# SCH.net
KiCad netlist of a schematic drawn in EasyEDA Pro
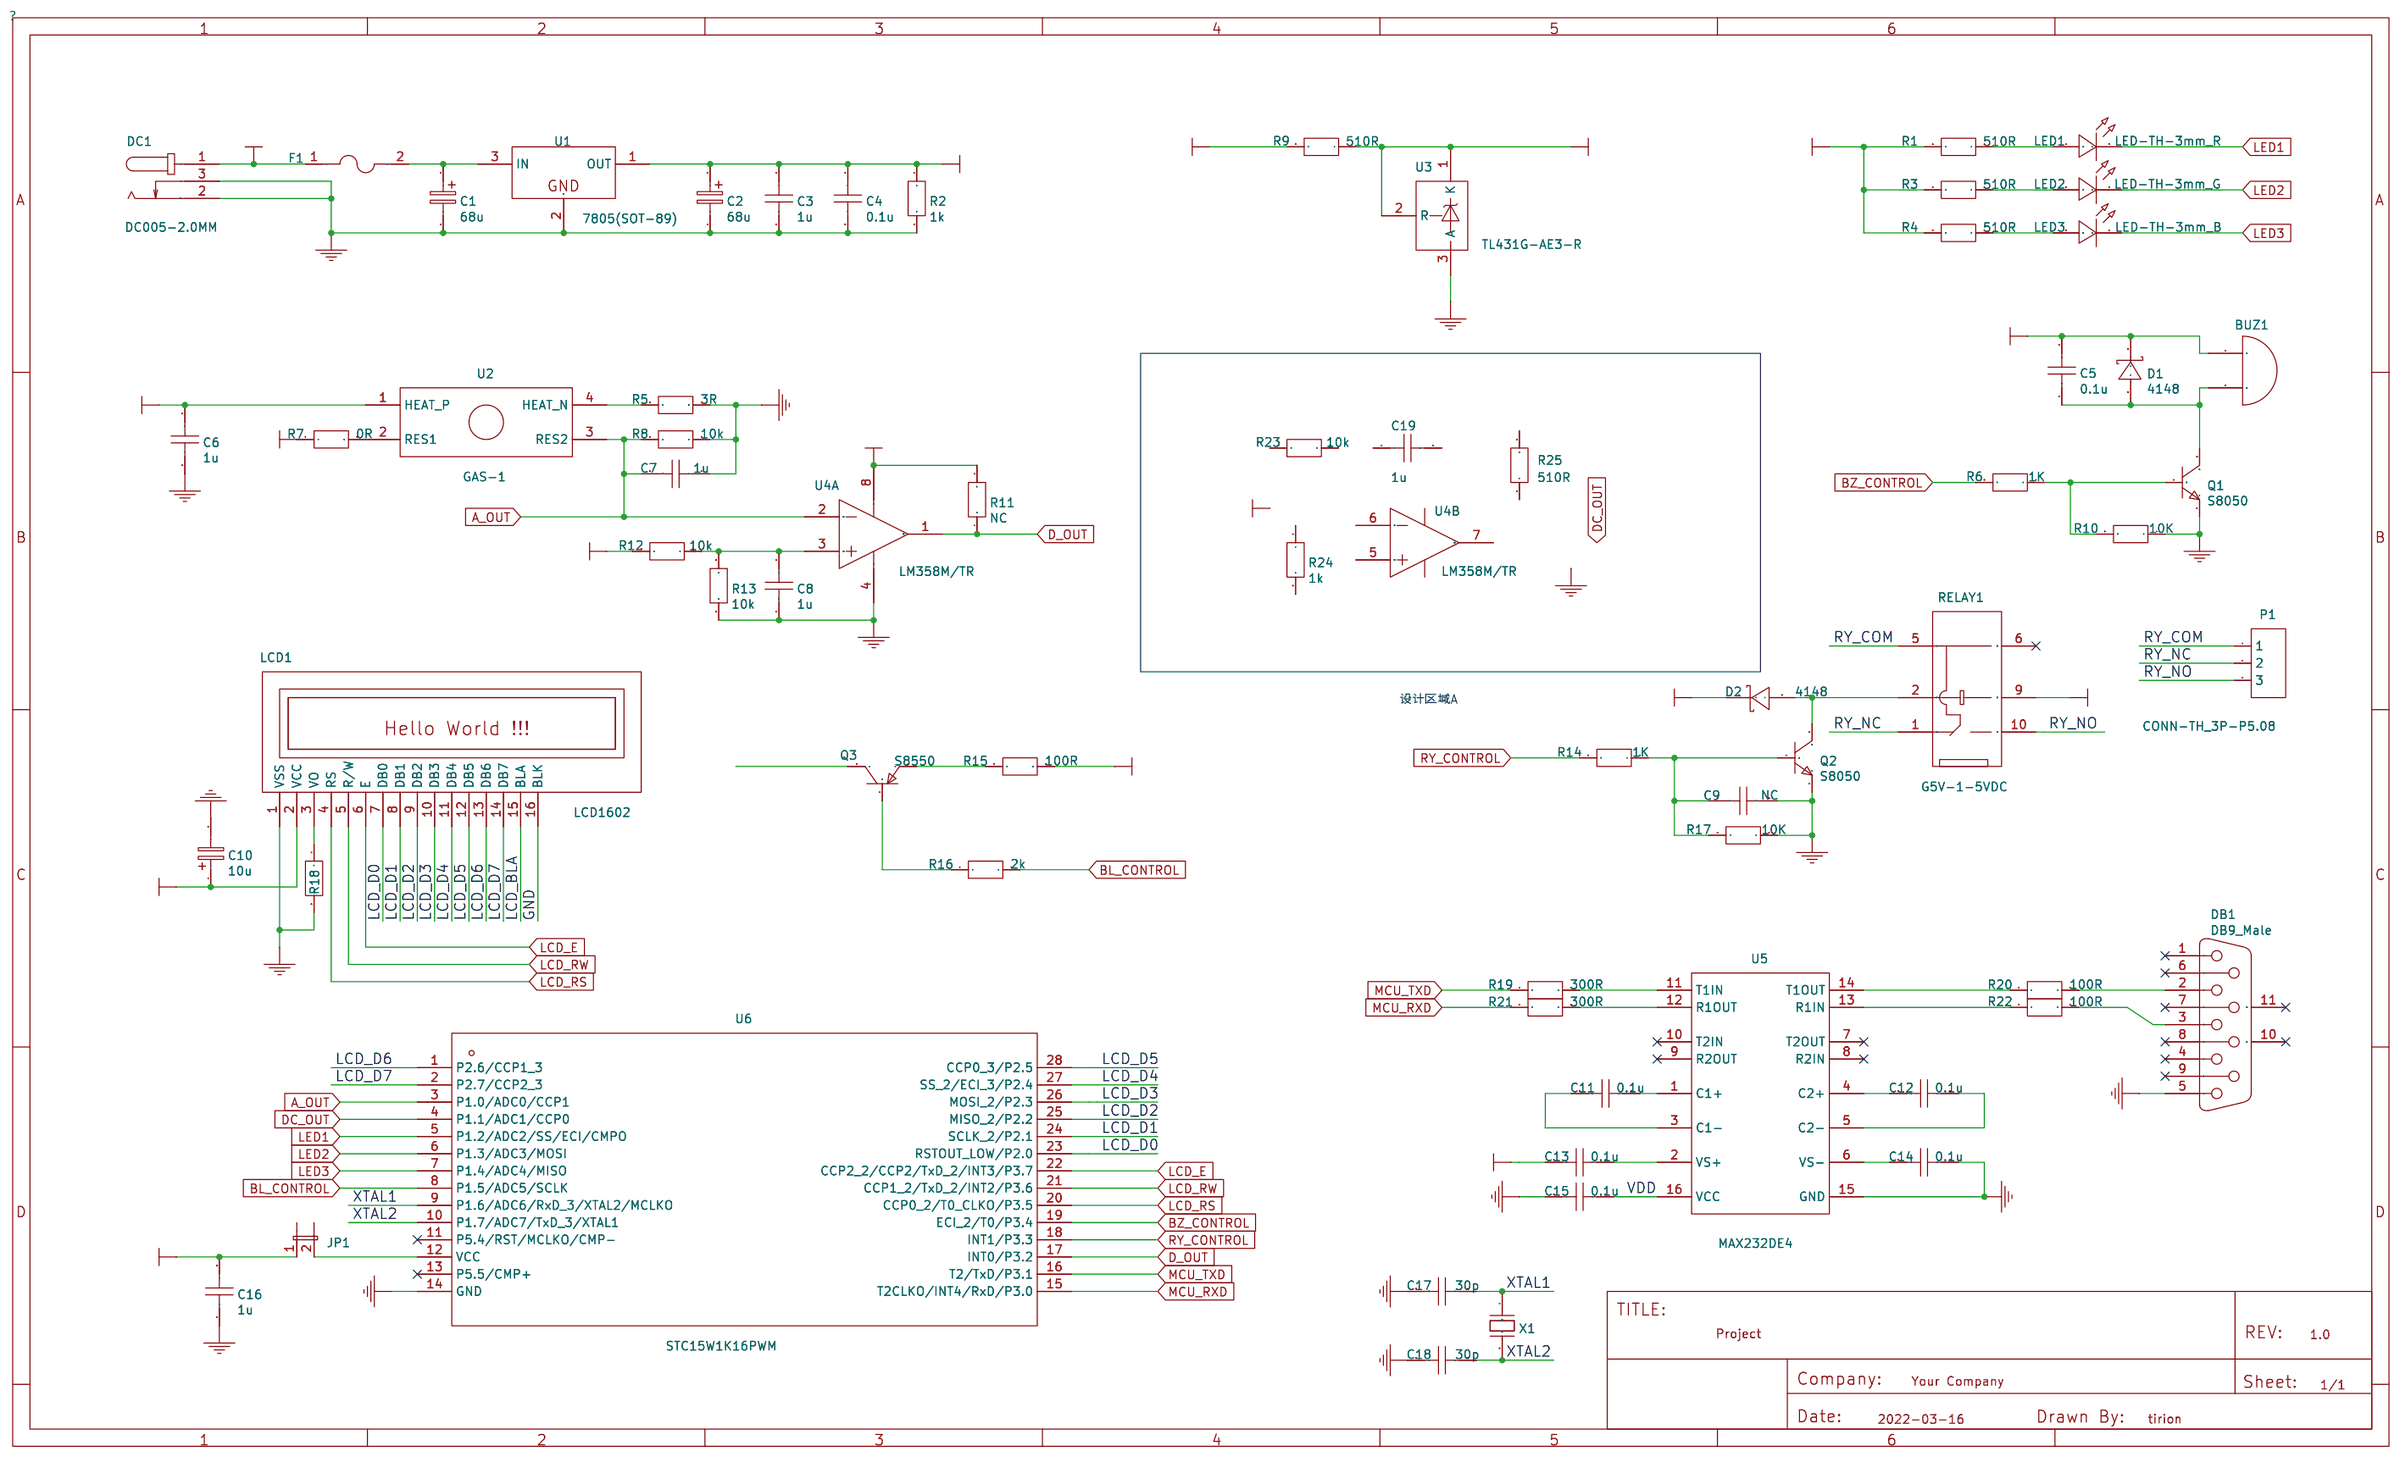
[diagram p0: schematic sheet]

(export (version "E")
  (design (tool "Eeschema 10.0.6"))
  (components
    (comp (ref "BUZ1") (value "BUZ1") (libsource (lib "easyedapro") (part "BUZ1")))
    (comp (ref "C1") (value "68u") (libsource (lib "easyedapro") (part "68u")))
    (comp (ref "C2") (value "68u") (libsource (lib "easyedapro") (part "68u")))
    (comp (ref "C3") (value "1u") (libsource (lib "easyedapro") (part "1u")))
    (comp (ref "C4") (value "0.1u") (libsource (lib "easyedapro") (part "0.1u")))
    (comp (ref "C5") (value "0.1u") (libsource (lib "easyedapro") (part "0.1u")))
    (comp (ref "C6") (value "1u") (libsource (lib "easyedapro") (part "1u")))
    (comp (ref "C7") (value "1u") (libsource (lib "easyedapro") (part "1u")))
    (comp (ref "C8") (value "1u") (libsource (lib "easyedapro") (part "1u")))
    (comp (ref "C9") (value "NC") (libsource (lib "easyedapro") (part "NC")))
    (comp (ref "C10") (value "10u") (libsource (lib "easyedapro") (part "10u")))
    (comp (ref "C11") (value "0.1u") (libsource (lib "easyedapro") (part "0.1u")))
    (comp (ref "C12") (value "0.1u") (libsource (lib "easyedapro") (part "0.1u")))
    (comp (ref "C13") (value "0.1u") (libsource (lib "easyedapro") (part "0.1u")))
    (comp (ref "C14") (value "0.1u") (libsource (lib "easyedapro") (part "0.1u")))
    (comp (ref "C15") (value "0.1u") (libsource (lib "easyedapro") (part "0.1u")))
    (comp (ref "C16") (value "1u") (libsource (lib "easyedapro") (part "1u")))
    (comp (ref "C17") (value "30p") (libsource (lib "easyedapro") (part "30p")))
    (comp (ref "C18") (value "30p") (libsource (lib "easyedapro") (part "30p")))
    (comp (ref "C19") (value "1u") (libsource (lib "easyedapro") (part "1u")))
    (comp (ref "D1")
      (value "4148")
      (fields (field (name "Manufacturer Part") "SS14") (field (name "Manufacturer") "MDD"))
      (libsource (lib "easyedapro") (part "4148"))
    )
    (comp (ref "D2")
      (value "4148")
      (fields (field (name "Manufacturer Part") "SS14") (field (name "Manufacturer") "MDD"))
      (libsource (lib "easyedapro") (part "4148"))
    )
    (comp (ref "DB1")
      (value "DB9_Male")
      (fields (field (name "Manufacturer") "Amphenol"))
      (libsource (lib "easyedapro") (part "DB9_Male"))
    )
    (comp (ref "DC1")
      (value "DC005-2.0MM")
      (fields (field (name "Manufacturer") "SOFNG"))
      (libsource (lib "easyedapro") (part "DC005-2.0MM"))
    )
    (comp (ref "F1") (value "FUSE_F1812_FUSE") (libsource (lib "easyedapro") (part "FUSE_F1812_FUSE")))
    (comp (ref "JP1") (value "JUMPER2") (libsource (lib "easyedapro") (part "JUMPER2")))
    (comp (ref "LCD1")
      (value "LCD1602")
      (fields
        (field (name "Manufacturer Part") "LCM1602K-NSW-BBW")
        (field (name "Manufacturer") "LONTECH(厦门龙特)")
      )
      (libsource (lib "easyedapro") (part "LCD1602"))
    )
    (comp (ref "LED1")
      (value "LED-TH-3mm_R")
      (fields
        (field (name "Manufacturer Part") "204-10SDRD/S530-A3-L")
        (field (name "Manufacturer") "EVERLIGHT(台湾亿光)")
      )
      (libsource (lib "easyedapro") (part "LED-TH-3mm_R"))
    )
    (comp (ref "LED2")
      (value "LED-TH-3mm_G")
      (fields
        (field (name "Manufacturer Part") "204-10SYGD/S530-E3")
        (field (name "Manufacturer") "EVERLIGHT(台湾亿光)")
      )
      (libsource (lib "easyedapro") (part "LED-TH-3mm_G"))
    )
    (comp (ref "LED3")
      (value "LED-TH-3mm_B")
      (fields
        (field (name "Manufacturer Part") "204-10SUBC/S400-A4")
        (field (name "Manufacturer") "EVERLIGHT(台湾亿光)")
      )
      (libsource (lib "easyedapro") (part "LED-TH-3mm_B"))
    )
    (comp (ref "P1") (value "CONN-TH_3P-P5.08") (libsource (lib "easyedapro") (part "CONN-TH_3P-P5.08")))
    (comp (ref "Q1")
      (value "S8050")
      (fields (field (name "Manufacturer") "JSMSEMI"))
      (libsource (lib "easyedapro") (part "S8050"))
    )
    (comp (ref "Q2")
      (value "S8050")
      (fields (field (name "Manufacturer") "JSMSEMI"))
      (libsource (lib "easyedapro") (part "S8050"))
    )
    (comp (ref "Q3")
      (value "S8550")
      (fields
        (field (name "Manufacturer Part") "S8550-H")
        (field (name "Manufacturer") "Yangzhou Yangjie Elec Tech")
      )
      (libsource (lib "easyedapro") (part "S8550"))
    )
    (comp (ref "R1") (value "510R") (libsource (lib "easyedapro") (part "510R")))
    (comp (ref "R2") (value "1k") (libsource (lib "easyedapro") (part "1k")))
    (comp (ref "R3") (value "510R") (libsource (lib "easyedapro") (part "510R")))
    (comp (ref "R4") (value "510R") (libsource (lib "easyedapro") (part "510R")))
    (comp (ref "R5") (value "3R") (libsource (lib "easyedapro") (part "3R")))
    (comp (ref "R6") (value "1K") (libsource (lib "easyedapro") (part "1K")))
    (comp (ref "R7") (value "0R") (libsource (lib "easyedapro") (part "0R")))
    (comp (ref "R8") (value "10k") (libsource (lib "easyedapro") (part "10k")))
    (comp (ref "R9") (value "510R") (libsource (lib "easyedapro") (part "510R")))
    (comp (ref "R10") (value "10K") (libsource (lib "easyedapro") (part "10K")))
    (comp (ref "R11") (value "NC") (libsource (lib "") (part "NC_1")))
    (comp (ref "R12") (value "10k") (libsource (lib "easyedapro") (part "10k")))
    (comp (ref "R13") (value "10k") (libsource (lib "easyedapro") (part "10k")))
    (comp (ref "R14") (value "1K") (libsource (lib "easyedapro") (part "1K")))
    (comp (ref "R15") (value "100R") (libsource (lib "easyedapro") (part "100R")))
    (comp (ref "R16") (value "2k") (libsource (lib "easyedapro") (part "2k")))
    (comp (ref "R17") (value "10K") (libsource (lib "easyedapro") (part "10K")))
    (comp (ref "R18") (value "10k") (libsource (lib "easyedapro") (part "10k")))
    (comp (ref "R19") (value "300R") (libsource (lib "easyedapro") (part "300R")))
    (comp (ref "R20") (value "100R") (libsource (lib "easyedapro") (part "100R")))
    (comp (ref "R21") (value "300R") (libsource (lib "easyedapro") (part "300R")))
    (comp (ref "R22") (value "100R") (libsource (lib "easyedapro") (part "100R")))
    (comp (ref "R23") (value "10k") (libsource (lib "easyedapro") (part "10k")))
    (comp (ref "R24") (value "1k") (libsource (lib "easyedapro") (part "1k")))
    (comp (ref "R25") (value "510R") (libsource (lib "easyedapro") (part "510R")))
    (comp (ref "RELAY1")
      (value "G5V-1-5VDC")
      (fields (field (name "Manufacturer") "OMRON"))
      (libsource (lib "easyedapro") (part "G5V-1-5VDC"))
    )
    (comp (ref "U1")
      (value "7805(SOT-89)")
      (fields (field (name "Manufacturer Part") "CJ78L05") (field (name "Manufacturer") "CJ"))
      (libsource (lib "easyedapro") (part "7805(SOT-89)"))
    )
    (comp (ref "U2") (value "GAS-1") (libsource (lib "easyedapro") (part "GAS-1")))
    (comp (ref "U3")
      (value "TL431G-AE3-R")
      (fields (field (name "Manufacturer") "UTC"))
      (libsource (lib "easyedapro") (part "TL431G-AE3-R"))
    )
    (comp (ref "U4")
      (value "LM358M/TR")
      (fields (field (name "Manufacturer") "HGSEMI"))
      (libsource (lib "easyedapro") (part "LM358M/TR"))
    )
    (comp (ref "U5") (value "MAX232DE4") (libsource (lib "easyedapro") (part "MAX232DE4")))
    (comp (ref "U6")
      (value "STC15W1K16PWM")
      (fields (field (name "Manufacturer") "STC"))
      (libsource (lib "easyedapro") (part "STC15W1K16PWM"))
    )
    (comp (ref "X1")
      (value "12MHZ")
      (fields (field (name "Manufacturer Part") "X49UD12MSD2SC") (field (name "Manufacturer") "LCSC"))
      (libsource (lib "easyedapro") (part "12MHZ"))
    )
  )
  (nets
    (net (code "1") (name "/LCD_BLA") (class "Default")
      (node (ref "LCD1") (pin "15") (pinfunction "BLA_15") (pintype "input"))
    )
    (net (code "2") (name "/LCD_D0") (class "Default")
      (node (ref "LCD1") (pin "7") (pinfunction "DB0_7") (pintype "input"))
      (node (ref "U6") (pin "23") (pinfunction "RSTOUT_LOW/P2.0_23") (pintype "input"))
    )
    (net (code "3") (name "/LCD_D1") (class "Default")
      (node (ref "LCD1") (pin "8") (pinfunction "DB1_8") (pintype "input"))
      (node (ref "U6") (pin "24") (pinfunction "SCLK_2/P2.1_24") (pintype "input"))
    )
    (net (code "4") (name "/LCD_D2") (class "Default")
      (node (ref "LCD1") (pin "9") (pinfunction "DB2_9") (pintype "input"))
      (node (ref "U6") (pin "25") (pinfunction "MISO_2/P2.2_25") (pintype "input"))
    )
    (net (code "5") (name "/LCD_D3") (class "Default")
      (node (ref "LCD1") (pin "10") (pinfunction "DB3_10") (pintype "input"))
      (node (ref "U6") (pin "26") (pinfunction "MOSI_2/P2.3_26") (pintype "input"))
    )
    (net (code "6") (name "/LCD_D4") (class "Default")
      (node (ref "LCD1") (pin "11") (pinfunction "DB4_11") (pintype "input"))
      (node (ref "U6") (pin "27") (pinfunction "SS_2/ECI_3/P2.4_27") (pintype "input"))
    )
    (net (code "7") (name "/LCD_D5") (class "Default")
      (node (ref "LCD1") (pin "12") (pinfunction "DB5_12") (pintype "input"))
      (node (ref "U6") (pin "28") (pinfunction "CCP0_3/P2.5_28") (pintype "input"))
    )
    (net (code "8") (name "/LCD_D6") (class "Default")
      (node (ref "LCD1") (pin "13") (pinfunction "DB6_13") (pintype "input"))
      (node (ref "U6") (pin "1") (pinfunction "P2.6/CCP1_3_1") (pintype "input"))
    )
    (net (code "9") (name "/LCD_D7") (class "Default")
      (node (ref "LCD1") (pin "14") (pinfunction "DB7_14") (pintype "input"))
      (node (ref "U6") (pin "2") (pinfunction "P2.7/CCP2_3_2") (pintype "input"))
    )
    (net (code "10") (name "/RY_COM") (class "Default")
      (node (ref "P1") (pin "1") (pinfunction "1_1") (pintype "input"))
      (node (ref "RELAY1") (pin "5") (pinfunction "5_5") (pintype "input"))
    )
    (net (code "11") (name "/RY_NC") (class "Default")
      (node (ref "P1") (pin "2") (pinfunction "2_2") (pintype "input"))
      (node (ref "RELAY1") (pin "1") (pinfunction "1_1") (pintype "input"))
    )
    (net (code "12") (name "/RY_NO") (class "Default")
      (node (ref "P1") (pin "3") (pinfunction "3_3") (pintype "input"))
      (node (ref "RELAY1") (pin "10") (pinfunction "10_10") (pintype "input"))
    )
    (net (code "13") (name "/XTAL1") (class "Default")
      (node (ref "C17") (pin "1") (pinfunction "1_1") (pintype "input"))
      (node (ref "U6") (pin "9") (pinfunction "P1.6/ADC6/RxD_3/XTAL2/MCLKO_9") (pintype "input"))
      (node (ref "X1") (pin "1") (pinfunction "OSC1_1") (pintype "input"))
    )
    (net (code "14") (name "/XTAL2") (class "Default")
      (node (ref "C18") (pin "1") (pinfunction "1_1") (pintype "input"))
      (node (ref "U6") (pin "10") (pinfunction "P1.7/ADC7/TxD_3/XTAL1_10") (pintype "input"))
      (node (ref "X1") (pin "2") (pinfunction "OSC2_2") (pintype "input"))
    )
    (net (code "15") (name "A_OUT") (class "Default")
      (node (ref "C7") (pin "2") (pinfunction "2_2") (pintype "input"))
      (node (ref "R8") (pin "1") (pinfunction "1_1") (pintype "input"))
      (node (ref "U2") (pin "3") (pinfunction "RES2_3") (pintype "input"))
      (node (ref "U4") (pin "2") (pinfunction "1IN-_2") (pintype "input"))
      (node (ref "U6") (pin "3") (pinfunction "P1.0/ADC0/CCP1_3") (pintype "input"))
    )
    (net (code "16") (name "BL_CONTROL") (class "Default")
      (node (ref "R16") (pin "2") (pinfunction "2_2") (pintype "input"))
      (node (ref "U6") (pin "8") (pinfunction "P1.5/ADC5/SCLK_8") (pintype "input"))
    )
    (net (code "17") (name "BZ_CONTROL") (class "Default")
      (node (ref "R6") (pin "2") (pinfunction "2_2") (pintype "input"))
      (node (ref "U6") (pin "19") (pinfunction "ECI_2/T0/P3.4_19") (pintype "input"))
    )
    (net (code "18") (name "DC_IN") (class "Default")
      (node (ref "DC1") (pin "1") (pinfunction "1_1") (pintype "input"))
      (node (ref "F1") (pin "1") (pinfunction "1_1") (pintype "input"))
    )
    (net (code "19") (name "DC_OUT") (class "Default")
      (node (ref "U6") (pin "4") (pinfunction "P1.1/ADC1/CCP0_4") (pintype "input"))
    )
    (net (code "20") (name "D_OUT") (class "Default")
      (node (ref "R11") (pin "1") (pinfunction "1_1") (pintype "input"))
      (node (ref "U4") (pin "1") (pinfunction "1OUT_1") (pintype "output"))
      (node (ref "U6") (pin "17") (pinfunction "INT0/P3.2_17") (pintype "input"))
    )
    (net (code "21") (name "GND") (class "Default")
      (node (ref "C1") (pin "2") (pinfunction "2_2") (pintype "input"))
      (node (ref "C10") (pin "2") (pinfunction "2_2") (pintype "input"))
      (node (ref "C14") (pin "2") (pinfunction "2_2") (pintype "input"))
      (node (ref "C15") (pin "1") (pinfunction "1_1") (pintype "input"))
      (node (ref "C16") (pin "1") (pinfunction "1_1") (pintype "input"))
      (node (ref "C17") (pin "2") (pinfunction "2_2") (pintype "input"))
      (node (ref "C18") (pin "2") (pinfunction "2_2") (pintype "input"))
      (node (ref "C2") (pin "2") (pinfunction "2_2") (pintype "input"))
      (node (ref "C3") (pin "2") (pinfunction "2_2") (pintype "input"))
      (node (ref "C4") (pin "2") (pinfunction "2_2") (pintype "input"))
      (node (ref "C6") (pin "1") (pinfunction "1_1") (pintype "input"))
      (node (ref "C7") (pin "1") (pinfunction "1_1") (pintype "input"))
      (node (ref "C8") (pin "2") (pinfunction "2_2") (pintype "input"))
      (node (ref "C9") (pin "2") (pinfunction "2_2") (pintype "input"))
      (node (ref "DB1") (pin "5") (pinfunction "5_5") (pintype "input"))
      (node (ref "DC1") (pin "2") (pinfunction "2_2") (pintype "input"))
      (node (ref "DC1") (pin "3") (pinfunction "3_3") (pintype "input"))
      (node (ref "LCD1") (pin "1") (pinfunction "VSS_1") (pintype "input"))
      (node (ref "LCD1") (pin "16") (pinfunction "BLK_16") (pintype "input"))
      (node (ref "Q1") (pin "2") (pinfunction "E_2") (pintype "input"))
      (node (ref "Q2") (pin "2") (pinfunction "E_2") (pintype "input"))
      (node (ref "R10") (pin "1") (pinfunction "1_1") (pintype "input"))
      (node (ref "R13") (pin "2") (pinfunction "2_2") (pintype "input"))
      (node (ref "R17") (pin "1") (pinfunction "1_1") (pintype "input"))
      (node (ref "R18") (pin "2") (pinfunction "2_2") (pintype "input"))
      (node (ref "R2") (pin "2") (pinfunction "2_2") (pintype "input"))
      (node (ref "R5") (pin "2") (pinfunction "2_2") (pintype "input"))
      (node (ref "R8") (pin "2") (pinfunction "2_2") (pintype "input"))
      (node (ref "U1") (pin "2") (pinfunction "GND_2") (pintype "input"))
      (node (ref "U3") (pin "3") (pinfunction "A_3") (pintype "input"))
      (node (ref "U4") (pin "4") (pinfunction "GND_4") (pintype "input"))
      (node (ref "U5") (pin "15") (pinfunction "GND_15") (pintype "input"))
      (node (ref "U6") (pin "14") (pinfunction "GND_14") (pintype "input"))
    )
    (net (code "22") (name "LCD_E") (class "Default")
      (node (ref "LCD1") (pin "6") (pinfunction "E_6") (pintype "input"))
      (node (ref "U6") (pin "22") (pinfunction "CCP2_2/CCP2/TxD_2/INT3/P3.7_22") (pintype "input"))
    )
    (net (code "23") (name "LCD_RS") (class "Default")
      (node (ref "LCD1") (pin "4") (pinfunction "RS_4") (pintype "input"))
      (node (ref "U6") (pin "20") (pinfunction "CCP0_2/T0_CLKO/P3.5_20") (pintype "input"))
    )
    (net (code "24") (name "LCD_RW") (class "Default")
      (node (ref "LCD1") (pin "5") (pinfunction "R/W_5") (pintype "input"))
      (node (ref "U6") (pin "21") (pinfunction "CCP1_2/TxD_2/INT2/P3.6_21") (pintype "input"))
    )
    (net (code "25") (name "LED1") (class "Default")
      (node (ref "LED1") (pin "2") (pinfunction "2_2") (pintype "input"))
      (node (ref "U6") (pin "5") (pinfunction "P1.2/ADC2/SS/ECI/CMPO_5") (pintype "input"))
    )
    (net (code "26") (name "LED2") (class "Default")
      (node (ref "LED2") (pin "2") (pinfunction "2_2") (pintype "input"))
      (node (ref "U6") (pin "6") (pinfunction "P1.3/ADC3/MOSI_6") (pintype "input"))
    )
    (net (code "27") (name "LED3") (class "Default")
      (node (ref "LED3") (pin "2") (pinfunction "2_2") (pintype "input"))
      (node (ref "U6") (pin "7") (pinfunction "P1.4/ADC4/MISO_7") (pintype "input"))
    )
    (net (code "28") (name "MCU_RXD") (class "Default")
      (node (ref "R21") (pin "1") (pinfunction "1_1") (pintype "input"))
      (node (ref "U6") (pin "15") (pinfunction "T2CLKO/INT4/RxD/P3.0_15") (pintype "input"))
    )
    (net (code "29") (name "MCU_TXD") (class "Default")
      (node (ref "R19") (pin "1") (pinfunction "1_1") (pintype "input"))
      (node (ref "U6") (pin "16") (pinfunction "T2/TxD/P3.1_16") (pintype "input"))
    )
    (net (code "30") (name "Net-(BUZ1-B)") (class "Default")
      (node (ref "BUZ1") (pin "2") (pinfunction "B_2") (pintype "input"))
      (node (ref "C5") (pin "1") (pinfunction "1_1") (pintype "input"))
      (node (ref "D1") (pin "2") (pinfunction "A_2") (pintype "input"))
      (node (ref "Q1") (pin "3") (pinfunction "C_3") (pintype "input"))
    )
    (net (code "31") (name "Net-(D2-A)") (class "Default")
      (node (ref "D2") (pin "2") (pinfunction "A_2") (pintype "input"))
      (node (ref "Q2") (pin "3") (pinfunction "C_3") (pintype "input"))
      (node (ref "RELAY1") (pin "2") (pinfunction "2_2") (pintype "input"))
    )
    (net (code "32") (name "Net-(DB1-Pad2)") (class "Default")
      (node (ref "DB1") (pin "2") (pinfunction "2_2") (pintype "input"))
      (node (ref "R20") (pin "2") (pinfunction "2_2") (pintype "input"))
    )
    (net (code "33") (name "Net-(DB1-Pad3)") (class "Default")
      (node (ref "DB1") (pin "3") (pinfunction "3_3") (pintype "input"))
      (node (ref "R22") (pin "2") (pinfunction "2_2") (pintype "input"))
    )
    (net (code "34") (name "Net-(LCD1-VO)") (class "Default")
      (node (ref "LCD1") (pin "3") (pinfunction "VO_3") (pintype "input"))
      (node (ref "R18") (pin "1") (pinfunction "1_1") (pintype "input"))
    )
    (net (code "35") (name "Net-(LED1-Pad1)") (class "Default")
      (node (ref "LED1") (pin "1") (pinfunction "1_1") (pintype "input"))
      (node (ref "R1") (pin "1") (pinfunction "1_1") (pintype "input"))
    )
    (net (code "36") (name "Net-(LED2-Pad1)") (class "Default")
      (node (ref "LED2") (pin "1") (pinfunction "1_1") (pintype "input"))
      (node (ref "R3") (pin "1") (pinfunction "1_1") (pintype "input"))
    )
    (net (code "37") (name "Net-(LED3-Pad1)") (class "Default")
      (node (ref "LED3") (pin "1") (pinfunction "1_1") (pintype "input"))
      (node (ref "R4") (pin "1") (pinfunction "1_1") (pintype "input"))
    )
    (net (code "38") (name "Net-(Q1-B)") (class "Default")
      (node (ref "Q1") (pin "1") (pinfunction "B_1") (pintype "input"))
      (node (ref "R10") (pin "2") (pinfunction "2_2") (pintype "input"))
      (node (ref "R6") (pin "1") (pinfunction "1_1") (pintype "input"))
    )
    (net (code "39") (name "Net-(Q2-B)") (class "Default")
      (node (ref "C9") (pin "1") (pinfunction "1_1") (pintype "input"))
      (node (ref "Q2") (pin "1") (pinfunction "B_1") (pintype "input"))
      (node (ref "R14") (pin "1") (pinfunction "1_1") (pintype "input"))
      (node (ref "R17") (pin "2") (pinfunction "2_2") (pintype "input"))
    )
    (net (code "40") (name "Net-(Q3-B)") (class "Default")
      (node (ref "Q3") (pin "1") (pinfunction "B_1") (pintype "input"))
      (node (ref "R16") (pin "1") (pinfunction "1_1") (pintype "input"))
    )
    (net (code "41") (name "Net-(Q3-E)") (class "Default")
      (node (ref "Q3") (pin "2") (pinfunction "E_2") (pintype "input"))
      (node (ref "R15") (pin "1") (pinfunction "1_1") (pintype "input"))
    )
    (net (code "42") (name "Net-(U1-IN)") (class "Default")
      (node (ref "C1") (pin "1") (pinfunction "1_1") (pintype "input"))
      (node (ref "F1") (pin "2") (pinfunction "2_2") (pintype "input"))
      (node (ref "U1") (pin "3") (pinfunction "IN_3") (pintype "input"))
    )
    (net (code "43") (name "Net-(U2-HEAT_N)") (class "Default")
      (node (ref "R5") (pin "1") (pinfunction "1_1") (pintype "input"))
      (node (ref "U2") (pin "4") (pinfunction "HEAT_N_4") (pintype "input"))
    )
    (net (code "44") (name "Net-(U2-RES1)") (class "Default")
      (node (ref "R7") (pin "2") (pinfunction "2_2") (pintype "input"))
      (node (ref "U2") (pin "2") (pinfunction "RES1_2") (pintype "input"))
    )
    (net (code "45") (name "Net-(U4A-1IN+)") (class "Default")
      (node (ref "C8") (pin "1") (pinfunction "1_1") (pintype "input"))
      (node (ref "R12") (pin "1") (pinfunction "1_1") (pintype "input"))
      (node (ref "R13") (pin "1") (pinfunction "1_1") (pintype "input"))
      (node (ref "U4") (pin "3") (pinfunction "1IN+_3") (pintype "input"))
    )
    (net (code "46") (name "Net-(U5-C1+)") (class "Default")
      (node (ref "C11") (pin "2") (pinfunction "2_2") (pintype "input"))
      (node (ref "U5") (pin "1") (pinfunction "C1+_1") (pintype "input"))
    )
    (net (code "47") (name "Net-(U5-C1-)") (class "Default")
      (node (ref "C11") (pin "1") (pinfunction "1_1") (pintype "input"))
      (node (ref "U5") (pin "3") (pinfunction "C1-_3") (pintype "input"))
    )
    (net (code "48") (name "Net-(U5-C2+)") (class "Default")
      (node (ref "C12") (pin "1") (pinfunction "1_1") (pintype "input"))
      (node (ref "U5") (pin "4") (pinfunction "C2+_4") (pintype "input"))
    )
    (net (code "49") (name "Net-(U5-C2-)") (class "Default")
      (node (ref "C12") (pin "2") (pinfunction "2_2") (pintype "input"))
      (node (ref "U5") (pin "5") (pinfunction "C2-_5") (pintype "input"))
    )
    (net (code "50") (name "Net-(U5-R1IN)") (class "Default")
      (node (ref "R22") (pin "1") (pinfunction "1_1") (pintype "input"))
      (node (ref "U5") (pin "13") (pinfunction "R1IN_13") (pintype "input"))
    )
    (net (code "51") (name "Net-(U5-R1OUT)") (class "Default")
      (node (ref "R21") (pin "2") (pinfunction "2_2") (pintype "input"))
      (node (ref "U5") (pin "12") (pinfunction "R1OUT_12") (pintype "output"))
    )
    (net (code "52") (name "Net-(U5-T1IN)") (class "Default")
      (node (ref "R19") (pin "2") (pinfunction "2_2") (pintype "input"))
      (node (ref "U5") (pin "11") (pinfunction "T1IN_11") (pintype "input"))
    )
    (net (code "53") (name "Net-(U5-T1OUT)") (class "Default")
      (node (ref "R20") (pin "1") (pinfunction "1_1") (pintype "input"))
      (node (ref "U5") (pin "14") (pinfunction "T1OUT_14") (pintype "output"))
    )
    (net (code "54") (name "Net-(U5-VS+)") (class "Default")
      (node (ref "C13") (pin "2") (pinfunction "2_2") (pintype "input"))
      (node (ref "U5") (pin "2") (pinfunction "VS+_2") (pintype "input"))
    )
    (net (code "55") (name "Net-(U5-VS-)") (class "Default")
      (node (ref "C14") (pin "1") (pinfunction "1_1") (pintype "input"))
      (node (ref "U5") (pin "6") (pinfunction "VS-_6") (pintype "input"))
    )
    (net (code "56") (name "Net-(U6-VCC)") (class "Default")
      (node (ref "JP1") (pin "2") (pinfunction "2_2") (pintype "input"))
      (node (ref "U6") (pin "12") (pinfunction "VCC_12") (pintype "input"))
    )
    (net (code "57") (name "RY_CONTROL") (class "Default")
      (node (ref "R14") (pin "2") (pinfunction "2_2") (pintype "input"))
      (node (ref "U6") (pin "18") (pinfunction "INT1/P3.3_18") (pintype "input"))
    )
    (net (code "58") (name "VDD") (class "Default")
      (node (ref "BUZ1") (pin "1") (pinfunction "A_1") (pintype "input"))
      (node (ref "C10") (pin "1") (pinfunction "1_1") (pintype "input"))
      (node (ref "C13") (pin "1") (pinfunction "1_1") (pintype "input"))
      (node (ref "C15") (pin "2") (pinfunction "2_2") (pintype "input"))
      (node (ref "C16") (pin "2") (pinfunction "2_2") (pintype "input"))
      (node (ref "C2") (pin "1") (pinfunction "1_1") (pintype "input"))
      (node (ref "C3") (pin "1") (pinfunction "1_1") (pintype "input"))
      (node (ref "C4") (pin "1") (pinfunction "1_1") (pintype "input"))
      (node (ref "C5") (pin "2") (pinfunction "2_2") (pintype "input"))
      (node (ref "C6") (pin "2") (pinfunction "2_2") (pintype "input"))
      (node (ref "D1") (pin "1") (pinfunction "K_1") (pintype "input"))
      (node (ref "D2") (pin "1") (pinfunction "K_1") (pintype "input"))
      (node (ref "JP1") (pin "1") (pinfunction "1_1") (pintype "input"))
      (node (ref "LCD1") (pin "2") (pinfunction "VCC_2") (pintype "input"))
      (node (ref "R1") (pin "2") (pinfunction "2_2") (pintype "input"))
      (node (ref "R11") (pin "2") (pinfunction "2_2") (pintype "input"))
      (node (ref "R15") (pin "2") (pinfunction "2_2") (pintype "input"))
      (node (ref "R2") (pin "1") (pinfunction "1_1") (pintype "input"))
      (node (ref "R3") (pin "2") (pinfunction "2_2") (pintype "input"))
      (node (ref "R4") (pin "2") (pinfunction "2_2") (pintype "input"))
      (node (ref "R9") (pin "2") (pinfunction "2_2") (pintype "input"))
      (node (ref "RELAY1") (pin "9") (pinfunction "9_9") (pintype "input"))
      (node (ref "U1") (pin "1") (pinfunction "OUT_1") (pintype "input"))
      (node (ref "U2") (pin "1") (pinfunction "HEAT_P_1") (pintype "input"))
      (node (ref "U4") (pin "8") (pinfunction "VCC_8") (pintype "input"))
      (node (ref "U5") (pin "16") (pinfunction "VCC_16") (pintype "input"))
    )
    (net (code "59") (name "VREF") (class "Default")
      (node (ref "R12") (pin "2") (pinfunction "2_2") (pintype "input"))
      (node (ref "R7") (pin "1") (pinfunction "1_1") (pintype "input"))
      (node (ref "R9") (pin "1") (pinfunction "1_1") (pintype "input"))
      (node (ref "U3") (pin "1") (pinfunction "K_1") (pintype "input"))
      (node (ref "U3") (pin "2") (pinfunction "R_2") (pintype "input"))
    )
    (net (code "60") (name "unconnected-(C19-Pad1)") (class "Default")
      (node (ref "C19") (pin "1") (pinfunction "1_1") (pintype "input"))
    )
    (net (code "61") (name "unconnected-(C19-Pad2)") (class "Default")
      (node (ref "C19") (pin "2") (pinfunction "2_2") (pintype "input"))
    )
    (net (code "62") (name "unconnected-(DB1-MH1-Pad10)") (class "Default")
      (node (ref "DB1") (pin "10") (pinfunction "MH1_10") (pintype "input+no_connect"))
    )
    (net (code "63") (name "unconnected-(DB1-MH2-Pad11)") (class "Default")
      (node (ref "DB1") (pin "11") (pinfunction "MH2_11") (pintype "input+no_connect"))
    )
    (net (code "64") (name "unconnected-(DB1-Pad1)") (class "Default")
      (node (ref "DB1") (pin "1") (pinfunction "1_1") (pintype "input+no_connect"))
    )
    (net (code "65") (name "unconnected-(DB1-Pad4)") (class "Default")
      (node (ref "DB1") (pin "4") (pinfunction "4_4") (pintype "input+no_connect"))
    )
    (net (code "66") (name "unconnected-(DB1-Pad6)") (class "Default")
      (node (ref "DB1") (pin "6") (pinfunction "6_6") (pintype "input+no_connect"))
    )
    (net (code "67") (name "unconnected-(DB1-Pad7)") (class "Default")
      (node (ref "DB1") (pin "7") (pinfunction "7_7") (pintype "input+no_connect"))
    )
    (net (code "68") (name "unconnected-(DB1-Pad8)") (class "Default")
      (node (ref "DB1") (pin "8") (pinfunction "8_8") (pintype "input+no_connect"))
    )
    (net (code "69") (name "unconnected-(DB1-Pad9)") (class "Default")
      (node (ref "DB1") (pin "9") (pinfunction "9_9") (pintype "input+no_connect"))
    )
    (net (code "70") (name "unconnected-(Q3-C-Pad3)") (class "Default")
      (node (ref "Q3") (pin "3") (pinfunction "C_3") (pintype "input"))
    )
    (net (code "71") (name "unconnected-(R23-Pad1)") (class "Default")
      (node (ref "R23") (pin "1") (pinfunction "1_1") (pintype "input"))
    )
    (net (code "72") (name "unconnected-(R23-Pad2)") (class "Default")
      (node (ref "R23") (pin "2") (pinfunction "2_2") (pintype "input"))
    )
    (net (code "73") (name "unconnected-(R24-Pad1)") (class "Default")
      (node (ref "R24") (pin "1") (pinfunction "1_1") (pintype "input"))
    )
    (net (code "74") (name "unconnected-(R24-Pad2)") (class "Default")
      (node (ref "R24") (pin "2") (pinfunction "2_2") (pintype "input"))
    )
    (net (code "75") (name "unconnected-(R25-Pad1)") (class "Default")
      (node (ref "R25") (pin "1") (pinfunction "1_1") (pintype "input"))
    )
    (net (code "76") (name "unconnected-(R25-Pad2)") (class "Default")
      (node (ref "R25") (pin "2") (pinfunction "2_2") (pintype "input"))
    )
    (net (code "77") (name "unconnected-(RELAY1-Pad6)") (class "Default")
      (node (ref "RELAY1") (pin "6") (pinfunction "6_6") (pintype "input+no_connect"))
    )
    (net (code "78") (name "unconnected-(U4B-2IN+-Pad5)") (class "Default")
      (node (ref "U4") (pin "5") (pinfunction "2IN+_5") (pintype "input"))
    )
    (net (code "79") (name "unconnected-(U4B-2IN--Pad6)") (class "Default")
      (node (ref "U4") (pin "6") (pinfunction "2IN-_6") (pintype "input"))
    )
    (net (code "80") (name "unconnected-(U4B-2OUT-Pad7)") (class "Default")
      (node (ref "U4") (pin "7") (pinfunction "2OUT_7") (pintype "output"))
    )
    (net (code "81") (name "unconnected-(U5-R2IN-Pad8)") (class "Default")
      (node (ref "U5") (pin "8") (pinfunction "R2IN_8") (pintype "input+no_connect"))
    )
    (net (code "82") (name "unconnected-(U5-R2OUT-Pad9)") (class "Default")
      (node (ref "U5") (pin "9") (pinfunction "R2OUT_9") (pintype "output+no_connect"))
    )
    (net (code "83") (name "unconnected-(U5-T2IN-Pad10)") (class "Default")
      (node (ref "U5") (pin "10") (pinfunction "T2IN_10") (pintype "input+no_connect"))
    )
    (net (code "84") (name "unconnected-(U5-T2OUT-Pad7)") (class "Default")
      (node (ref "U5") (pin "7") (pinfunction "T2OUT_7") (pintype "output+no_connect"))
    )
    (net (code "85") (name "unconnected-(U6-P5.4{slash}RST{slash}MCLKO{slash}CMP--Pad11)") (class "Default")
      (node (ref "U6") (pin "11") (pinfunction "P5.4/RST/MCLKO/CMP-_11") (pintype "input+no_connect"))
    )
    (net (code "86") (name "unconnected-(U6-P5.5{slash}CMP+-Pad13)") (class "Default")
      (node (ref "U6") (pin "13") (pinfunction "P5.5/CMP+_13") (pintype "input+no_connect"))
    )
  )
)
